# IR180-19_5GF.net
KiCad netlist of a schematic drawn in Altium Designer
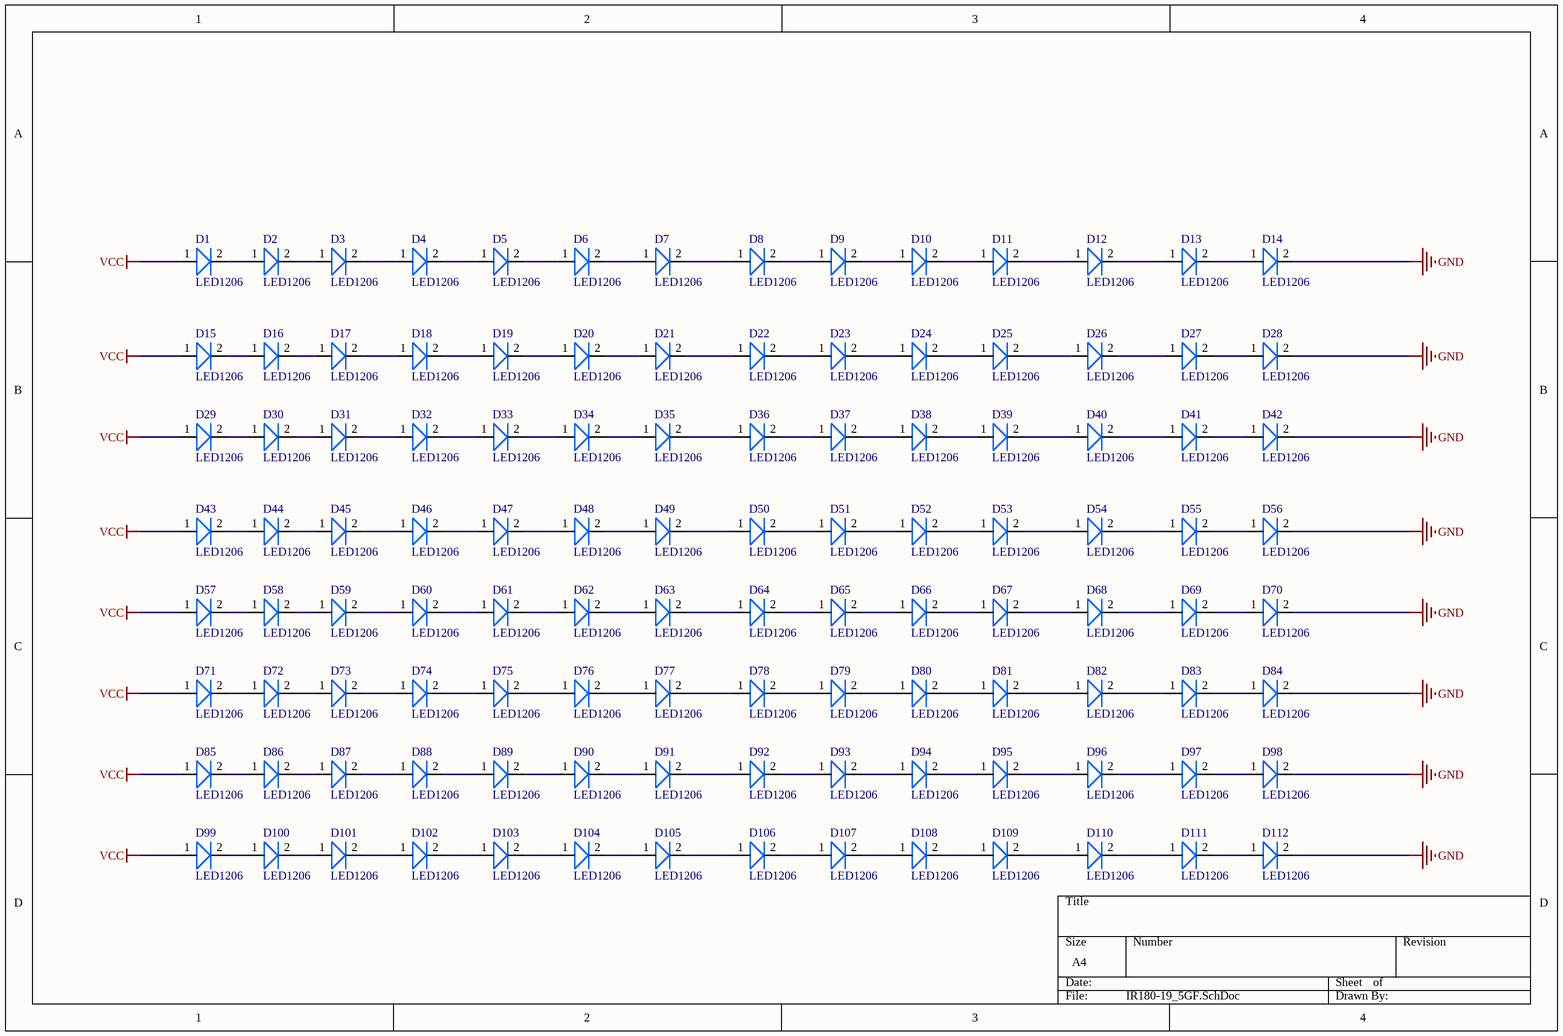
[diagram p0: IR180-19_5GF.SchDoc]

(export (version "E")
  (design (tool "Eeschema 10.0.6"))
  (components
    (comp (ref "D1")
      (value "LED1206")
      (footprint "myPCBLib:IRLED2835M")
      (libsource (lib "mySchLib") (part "LED1206"))
    )
    (comp (ref "D2")
      (value "LED1206")
      (footprint "myPCBLib:IRLED2835M")
      (libsource (lib "mySchLib") (part "LED1206"))
    )
    (comp (ref "D3")
      (value "LED1206")
      (footprint "myPCBLib:IRLED2835M")
      (libsource (lib "mySchLib") (part "LED1206"))
    )
    (comp (ref "D4")
      (value "LED1206")
      (footprint "myPCBLib:IRLED2835M")
      (libsource (lib "mySchLib") (part "LED1206"))
    )
    (comp (ref "D5")
      (value "LED1206")
      (footprint "myPCBLib:IRLED2835M")
      (libsource (lib "mySchLib") (part "LED1206"))
    )
    (comp (ref "D6")
      (value "LED1206")
      (footprint "myPCBLib:IRLED2835M")
      (libsource (lib "mySchLib") (part "LED1206"))
    )
    (comp (ref "D7")
      (value "LED1206")
      (footprint "myPCBLib:IRLED2835M")
      (libsource (lib "mySchLib") (part "LED1206"))
    )
    (comp (ref "D8")
      (value "LED1206")
      (footprint "myPCBLib:IRLED2835M")
      (libsource (lib "mySchLib") (part "LED1206"))
    )
    (comp (ref "D9")
      (value "LED1206")
      (footprint "myPCBLib:IRLED2835M")
      (libsource (lib "mySchLib") (part "LED1206"))
    )
    (comp (ref "D10")
      (value "LED1206")
      (footprint "myPCBLib:IRLED2835M")
      (libsource (lib "mySchLib") (part "LED1206"))
    )
    (comp (ref "D11")
      (value "LED1206")
      (footprint "myPCBLib:IRLED2835M")
      (libsource (lib "mySchLib") (part "LED1206"))
    )
    (comp (ref "D12")
      (value "LED1206")
      (footprint "myPCBLib:IRLED2835M")
      (libsource (lib "mySchLib") (part "LED1206"))
    )
    (comp (ref "D13")
      (value "LED1206")
      (footprint "myPCBLib:IRLED2835M")
      (libsource (lib "mySchLib") (part "LED1206"))
    )
    (comp (ref "D14")
      (value "LED1206")
      (footprint "myPCBLib:IRLED2835M")
      (libsource (lib "mySchLib") (part "LED1206"))
    )
    (comp (ref "D15")
      (value "LED1206")
      (footprint "myPCBLib:IRLED2835M")
      (libsource (lib "mySchLib") (part "LED1206"))
    )
    (comp (ref "D16")
      (value "LED1206")
      (footprint "myPCBLib:IRLED2835M")
      (libsource (lib "mySchLib") (part "LED1206"))
    )
    (comp (ref "D17")
      (value "LED1206")
      (footprint "myPCBLib:IRLED2835M")
      (libsource (lib "mySchLib") (part "LED1206"))
    )
    (comp (ref "D18")
      (value "LED1206")
      (footprint "myPCBLib:IRLED2835M")
      (libsource (lib "mySchLib") (part "LED1206"))
    )
    (comp (ref "D19")
      (value "LED1206")
      (footprint "myPCBLib:IRLED2835M")
      (libsource (lib "mySchLib") (part "LED1206"))
    )
    (comp (ref "D20")
      (value "LED1206")
      (footprint "myPCBLib:IRLED2835M")
      (libsource (lib "mySchLib") (part "LED1206"))
    )
    (comp (ref "D21")
      (value "LED1206")
      (footprint "myPCBLib:IRLED2835M")
      (libsource (lib "mySchLib") (part "LED1206"))
    )
    (comp (ref "D22")
      (value "LED1206")
      (footprint "myPCBLib:IRLED2835M")
      (libsource (lib "mySchLib") (part "LED1206"))
    )
    (comp (ref "D23")
      (value "LED1206")
      (footprint "myPCBLib:IRLED2835M")
      (libsource (lib "mySchLib") (part "LED1206"))
    )
    (comp (ref "D24")
      (value "LED1206")
      (footprint "myPCBLib:IRLED2835M")
      (libsource (lib "mySchLib") (part "LED1206"))
    )
    (comp (ref "D25")
      (value "LED1206")
      (footprint "myPCBLib:IRLED2835M")
      (libsource (lib "mySchLib") (part "LED1206"))
    )
    (comp (ref "D26")
      (value "LED1206")
      (footprint "myPCBLib:IRLED2835M")
      (libsource (lib "mySchLib") (part "LED1206"))
    )
    (comp (ref "D27")
      (value "LED1206")
      (footprint "myPCBLib:IRLED2835M")
      (libsource (lib "mySchLib") (part "LED1206"))
    )
    (comp (ref "D28")
      (value "LED1206")
      (footprint "myPCBLib:IRLED2835M")
      (libsource (lib "mySchLib") (part "LED1206"))
    )
    (comp (ref "D29")
      (value "LED1206")
      (footprint "myPCBLib:IRLED2835M")
      (libsource (lib "mySchLib") (part "LED1206"))
    )
    (comp (ref "D30")
      (value "LED1206")
      (footprint "myPCBLib:IRLED2835M")
      (libsource (lib "mySchLib") (part "LED1206"))
    )
    (comp (ref "D31")
      (value "LED1206")
      (footprint "myPCBLib:IRLED2835M")
      (libsource (lib "mySchLib") (part "LED1206"))
    )
    (comp (ref "D32")
      (value "LED1206")
      (footprint "myPCBLib:IRLED2835M")
      (libsource (lib "mySchLib") (part "LED1206"))
    )
    (comp (ref "D33")
      (value "LED1206")
      (footprint "myPCBLib:IRLED2835M")
      (libsource (lib "mySchLib") (part "LED1206"))
    )
    (comp (ref "D34")
      (value "LED1206")
      (footprint "myPCBLib:IRLED2835M")
      (libsource (lib "mySchLib") (part "LED1206"))
    )
    (comp (ref "D35")
      (value "LED1206")
      (footprint "myPCBLib:IRLED2835M")
      (libsource (lib "mySchLib") (part "LED1206"))
    )
    (comp (ref "D36")
      (value "LED1206")
      (footprint "myPCBLib:IRLED2835M")
      (libsource (lib "mySchLib") (part "LED1206"))
    )
    (comp (ref "D37")
      (value "LED1206")
      (footprint "myPCBLib:IRLED2835M")
      (libsource (lib "mySchLib") (part "LED1206"))
    )
    (comp (ref "D38")
      (value "LED1206")
      (footprint "myPCBLib:IRLED2835M")
      (libsource (lib "mySchLib") (part "LED1206"))
    )
    (comp (ref "D39")
      (value "LED1206")
      (footprint "myPCBLib:IRLED2835M")
      (libsource (lib "mySchLib") (part "LED1206"))
    )
    (comp (ref "D40")
      (value "LED1206")
      (footprint "myPCBLib:IRLED2835M")
      (libsource (lib "mySchLib") (part "LED1206"))
    )
    (comp (ref "D41")
      (value "LED1206")
      (footprint "myPCBLib:IRLED2835M")
      (libsource (lib "mySchLib") (part "LED1206"))
    )
    (comp (ref "D42")
      (value "LED1206")
      (footprint "myPCBLib:IRLED2835M")
      (libsource (lib "mySchLib") (part "LED1206"))
    )
    (comp (ref "D43")
      (value "LED1206")
      (footprint "myPCBLib:IRLED2835M")
      (libsource (lib "mySchLib") (part "LED1206"))
    )
    (comp (ref "D44")
      (value "LED1206")
      (footprint "myPCBLib:IRLED2835M")
      (libsource (lib "mySchLib") (part "LED1206"))
    )
    (comp (ref "D45")
      (value "LED1206")
      (footprint "myPCBLib:IRLED2835M")
      (libsource (lib "mySchLib") (part "LED1206"))
    )
    (comp (ref "D46")
      (value "LED1206")
      (footprint "myPCBLib:IRLED2835M")
      (libsource (lib "mySchLib") (part "LED1206"))
    )
    (comp (ref "D47")
      (value "LED1206")
      (footprint "myPCBLib:IRLED2835M")
      (libsource (lib "mySchLib") (part "LED1206"))
    )
    (comp (ref "D48")
      (value "LED1206")
      (footprint "myPCBLib:IRLED2835M")
      (libsource (lib "mySchLib") (part "LED1206"))
    )
    (comp (ref "D49")
      (value "LED1206")
      (footprint "myPCBLib:IRLED2835M")
      (libsource (lib "mySchLib") (part "LED1206"))
    )
    (comp (ref "D50")
      (value "LED1206")
      (footprint "myPCBLib:IRLED2835M")
      (libsource (lib "mySchLib") (part "LED1206"))
    )
    (comp (ref "D51")
      (value "LED1206")
      (footprint "myPCBLib:IRLED2835M")
      (libsource (lib "mySchLib") (part "LED1206"))
    )
    (comp (ref "D52")
      (value "LED1206")
      (footprint "myPCBLib:IRLED2835M")
      (libsource (lib "mySchLib") (part "LED1206"))
    )
    (comp (ref "D53")
      (value "LED1206")
      (footprint "myPCBLib:IRLED2835M")
      (libsource (lib "mySchLib") (part "LED1206"))
    )
    (comp (ref "D54")
      (value "LED1206")
      (footprint "myPCBLib:IRLED2835M")
      (libsource (lib "mySchLib") (part "LED1206"))
    )
    (comp (ref "D55")
      (value "LED1206")
      (footprint "myPCBLib:IRLED2835M")
      (libsource (lib "mySchLib") (part "LED1206"))
    )
    (comp (ref "D56")
      (value "LED1206")
      (footprint "myPCBLib:IRLED2835M")
      (libsource (lib "mySchLib") (part "LED1206"))
    )
    (comp (ref "D57")
      (value "LED1206")
      (footprint "myPCBLib:IRLED2835M")
      (libsource (lib "mySchLib") (part "LED1206"))
    )
    (comp (ref "D58")
      (value "LED1206")
      (footprint "myPCBLib:IRLED2835M")
      (libsource (lib "mySchLib") (part "LED1206"))
    )
    (comp (ref "D59")
      (value "LED1206")
      (footprint "myPCBLib:IRLED2835M")
      (libsource (lib "mySchLib") (part "LED1206"))
    )
    (comp (ref "D60")
      (value "LED1206")
      (footprint "myPCBLib:IRLED2835M")
      (libsource (lib "mySchLib") (part "LED1206"))
    )
    (comp (ref "D61")
      (value "LED1206")
      (footprint "myPCBLib:IRLED2835M")
      (libsource (lib "mySchLib") (part "LED1206"))
    )
    (comp (ref "D62")
      (value "LED1206")
      (footprint "myPCBLib:IRLED2835M")
      (libsource (lib "mySchLib") (part "LED1206"))
    )
    (comp (ref "D63")
      (value "LED1206")
      (footprint "myPCBLib:IRLED2835M")
      (libsource (lib "mySchLib") (part "LED1206"))
    )
    (comp (ref "D64")
      (value "LED1206")
      (footprint "myPCBLib:IRLED2835M")
      (libsource (lib "mySchLib") (part "LED1206"))
    )
    (comp (ref "D65")
      (value "LED1206")
      (footprint "myPCBLib:IRLED2835M")
      (libsource (lib "mySchLib") (part "LED1206"))
    )
    (comp (ref "D66")
      (value "LED1206")
      (footprint "myPCBLib:IRLED2835M")
      (libsource (lib "mySchLib") (part "LED1206"))
    )
    (comp (ref "D67")
      (value "LED1206")
      (footprint "myPCBLib:IRLED2835M")
      (libsource (lib "mySchLib") (part "LED1206"))
    )
    (comp (ref "D68")
      (value "LED1206")
      (footprint "myPCBLib:IRLED2835M")
      (libsource (lib "mySchLib") (part "LED1206"))
    )
    (comp (ref "D69")
      (value "LED1206")
      (footprint "myPCBLib:IRLED2835M")
      (libsource (lib "mySchLib") (part "LED1206"))
    )
    (comp (ref "D70")
      (value "LED1206")
      (footprint "myPCBLib:IRLED2835M")
      (libsource (lib "mySchLib") (part "LED1206"))
    )
    (comp (ref "D71")
      (value "LED1206")
      (footprint "myPCBLib:IRLED2835M")
      (libsource (lib "mySchLib") (part "LED1206"))
    )
    (comp (ref "D72")
      (value "LED1206")
      (footprint "myPCBLib:IRLED2835M")
      (libsource (lib "mySchLib") (part "LED1206"))
    )
    (comp (ref "D73")
      (value "LED1206")
      (footprint "myPCBLib:IRLED2835M")
      (libsource (lib "mySchLib") (part "LED1206"))
    )
    (comp (ref "D74")
      (value "LED1206")
      (footprint "myPCBLib:IRLED2835M")
      (libsource (lib "mySchLib") (part "LED1206"))
    )
    (comp (ref "D75")
      (value "LED1206")
      (footprint "myPCBLib:IRLED2835M")
      (libsource (lib "mySchLib") (part "LED1206"))
    )
    (comp (ref "D76")
      (value "LED1206")
      (footprint "myPCBLib:IRLED2835M")
      (libsource (lib "mySchLib") (part "LED1206"))
    )
    (comp (ref "D77")
      (value "LED1206")
      (footprint "myPCBLib:IRLED2835M")
      (libsource (lib "mySchLib") (part "LED1206"))
    )
    (comp (ref "D78")
      (value "LED1206")
      (footprint "myPCBLib:IRLED2835M")
      (libsource (lib "mySchLib") (part "LED1206"))
    )
    (comp (ref "D79")
      (value "LED1206")
      (footprint "myPCBLib:IRLED2835M")
      (libsource (lib "mySchLib") (part "LED1206"))
    )
    (comp (ref "D80")
      (value "LED1206")
      (footprint "myPCBLib:IRLED2835M")
      (libsource (lib "mySchLib") (part "LED1206"))
    )
    (comp (ref "D81")
      (value "LED1206")
      (footprint "myPCBLib:IRLED2835M")
      (libsource (lib "mySchLib") (part "LED1206"))
    )
    (comp (ref "D82")
      (value "LED1206")
      (footprint "myPCBLib:IRLED2835M")
      (libsource (lib "mySchLib") (part "LED1206"))
    )
    (comp (ref "D83")
      (value "LED1206")
      (footprint "myPCBLib:IRLED2835M")
      (libsource (lib "mySchLib") (part "LED1206"))
    )
    (comp (ref "D84")
      (value "LED1206")
      (footprint "myPCBLib:IRLED2835M")
      (libsource (lib "mySchLib") (part "LED1206"))
    )
    (comp (ref "D85")
      (value "LED1206")
      (footprint "myPCBLib:IRLED2835M")
      (libsource (lib "mySchLib") (part "LED1206"))
    )
    (comp (ref "D86")
      (value "LED1206")
      (footprint "myPCBLib:IRLED2835M")
      (libsource (lib "mySchLib") (part "LED1206"))
    )
    (comp (ref "D87")
      (value "LED1206")
      (footprint "myPCBLib:IRLED2835M")
      (libsource (lib "mySchLib") (part "LED1206"))
    )
    (comp (ref "D88")
      (value "LED1206")
      (footprint "myPCBLib:IRLED2835M")
      (libsource (lib "mySchLib") (part "LED1206"))
    )
    (comp (ref "D89")
      (value "LED1206")
      (footprint "myPCBLib:IRLED2835M")
      (libsource (lib "mySchLib") (part "LED1206"))
    )
    (comp (ref "D90")
      (value "LED1206")
      (footprint "myPCBLib:IRLED2835M")
      (libsource (lib "mySchLib") (part "LED1206"))
    )
    (comp (ref "D91")
      (value "LED1206")
      (footprint "myPCBLib:IRLED2835M")
      (libsource (lib "mySchLib") (part "LED1206"))
    )
    (comp (ref "D92")
      (value "LED1206")
      (footprint "myPCBLib:IRLED2835M")
      (libsource (lib "mySchLib") (part "LED1206"))
    )
    (comp (ref "D93")
      (value "LED1206")
      (footprint "myPCBLib:IRLED2835M")
      (libsource (lib "mySchLib") (part "LED1206"))
    )
    (comp (ref "D94")
      (value "LED1206")
      (footprint "myPCBLib:IRLED2835M")
      (libsource (lib "mySchLib") (part "LED1206"))
    )
    (comp (ref "D95")
      (value "LED1206")
      (footprint "myPCBLib:IRLED2835M")
      (libsource (lib "mySchLib") (part "LED1206"))
    )
    (comp (ref "D96")
      (value "LED1206")
      (footprint "myPCBLib:IRLED2835M")
      (libsource (lib "mySchLib") (part "LED1206"))
    )
    (comp (ref "D97")
      (value "LED1206")
      (footprint "myPCBLib:IRLED2835M")
      (libsource (lib "mySchLib") (part "LED1206"))
    )
    (comp (ref "D98")
      (value "LED1206")
      (footprint "myPCBLib:IRLED2835M")
      (libsource (lib "mySchLib") (part "LED1206"))
    )
    (comp (ref "D99")
      (value "LED1206")
      (footprint "myPCBLib:IRLED2835M")
      (libsource (lib "mySchLib") (part "LED1206"))
    )
    (comp (ref "D100")
      (value "LED1206")
      (footprint "myPCBLib:IRLED2835M")
      (libsource (lib "mySchLib") (part "LED1206"))
    )
    (comp (ref "D101")
      (value "LED1206")
      (footprint "myPCBLib:IRLED2835M")
      (libsource (lib "mySchLib") (part "LED1206"))
    )
    (comp (ref "D102")
      (value "LED1206")
      (footprint "myPCBLib:IRLED2835M")
      (libsource (lib "mySchLib") (part "LED1206"))
    )
    (comp (ref "D103")
      (value "LED1206")
      (footprint "myPCBLib:IRLED2835M")
      (libsource (lib "mySchLib") (part "LED1206"))
    )
    (comp (ref "D104")
      (value "LED1206")
      (footprint "myPCBLib:IRLED2835M")
      (libsource (lib "mySchLib") (part "LED1206"))
    )
    (comp (ref "D105")
      (value "LED1206")
      (footprint "myPCBLib:IRLED2835M")
      (libsource (lib "mySchLib") (part "LED1206"))
    )
    (comp (ref "D106")
      (value "LED1206")
      (footprint "myPCBLib:IRLED2835M")
      (libsource (lib "mySchLib") (part "LED1206"))
    )
    (comp (ref "D107")
      (value "LED1206")
      (footprint "myPCBLib:IRLED2835M")
      (libsource (lib "mySchLib") (part "LED1206"))
    )
    (comp (ref "D108")
      (value "LED1206")
      (footprint "myPCBLib:IRLED2835M")
      (libsource (lib "mySchLib") (part "LED1206"))
    )
    (comp (ref "D109")
      (value "LED1206")
      (footprint "myPCBLib:IRLED2835M")
      (libsource (lib "mySchLib") (part "LED1206"))
    )
    (comp (ref "D110")
      (value "LED1206")
      (footprint "myPCBLib:IRLED2835M")
      (libsource (lib "mySchLib") (part "LED1206"))
    )
    (comp (ref "D111")
      (value "LED1206")
      (footprint "myPCBLib:IRLED2835M")
      (libsource (lib "mySchLib") (part "LED1206"))
    )
    (comp (ref "D112")
      (value "LED1206")
      (footprint "myPCBLib:IRLED2835M")
      (libsource (lib "mySchLib") (part "LED1206"))
    )
  )
  (nets
    (net (code "1") (name "GND") (class "Default")
      (node (ref "D112") (pin "2") (pinfunction "-_2") (pintype "open_collector"))
      (node (ref "D14") (pin "2") (pinfunction "-_2") (pintype "open_collector"))
      (node (ref "D28") (pin "2") (pinfunction "-_2") (pintype "open_collector"))
      (node (ref "D42") (pin "2") (pinfunction "-_2") (pintype "open_collector"))
      (node (ref "D56") (pin "2") (pinfunction "-_2") (pintype "open_collector"))
      (node (ref "D70") (pin "2") (pinfunction "-_2") (pintype "open_collector"))
      (node (ref "D84") (pin "2") (pinfunction "-_2") (pintype "open_collector"))
      (node (ref "D98") (pin "2") (pinfunction "-_2") (pintype "open_collector"))
    )
    (net (code "2") (name "Net-(D1--)") (class "Default")
      (node (ref "D1") (pin "2") (pinfunction "-_2") (pintype "open_collector"))
      (node (ref "D2") (pin "1") (pinfunction "+_1") (pintype "passive"))
    )
    (net (code "3") (name "Net-(D2--)") (class "Default")
      (node (ref "D2") (pin "2") (pinfunction "-_2") (pintype "open_collector"))
      (node (ref "D3") (pin "1") (pinfunction "+_1") (pintype "passive"))
    )
    (net (code "4") (name "Net-(D3--)") (class "Default")
      (node (ref "D3") (pin "2") (pinfunction "-_2") (pintype "open_collector"))
      (node (ref "D4") (pin "1") (pinfunction "+_1") (pintype "passive"))
    )
    (net (code "5") (name "Net-(D4--)") (class "Default")
      (node (ref "D4") (pin "2") (pinfunction "-_2") (pintype "open_collector"))
      (node (ref "D5") (pin "1") (pinfunction "+_1") (pintype "passive"))
    )
    (net (code "6") (name "Net-(D5--)") (class "Default")
      (node (ref "D5") (pin "2") (pinfunction "-_2") (pintype "open_collector"))
      (node (ref "D6") (pin "1") (pinfunction "+_1") (pintype "passive"))
    )
    (net (code "7") (name "Net-(D6--)") (class "Default")
      (node (ref "D6") (pin "2") (pinfunction "-_2") (pintype "open_collector"))
      (node (ref "D7") (pin "1") (pinfunction "+_1") (pintype "passive"))
    )
    (net (code "8") (name "Net-(D7--)") (class "Default")
      (node (ref "D7") (pin "2") (pinfunction "-_2") (pintype "open_collector"))
      (node (ref "D8") (pin "1") (pinfunction "+_1") (pintype "passive"))
    )
    (net (code "9") (name "Net-(D8--)") (class "Default")
      (node (ref "D8") (pin "2") (pinfunction "-_2") (pintype "open_collector"))
      (node (ref "D9") (pin "1") (pinfunction "+_1") (pintype "passive"))
    )
    (net (code "10") (name "Net-(D10-+)") (class "Default")
      (node (ref "D10") (pin "1") (pinfunction "+_1") (pintype "passive"))
      (node (ref "D9") (pin "2") (pinfunction "-_2") (pintype "open_collector"))
    )
    (net (code "11") (name "Net-(D10--)") (class "Default")
      (node (ref "D10") (pin "2") (pinfunction "-_2") (pintype "open_collector"))
      (node (ref "D11") (pin "1") (pinfunction "+_1") (pintype "passive"))
    )
    (net (code "12") (name "Net-(D11--)") (class "Default")
      (node (ref "D11") (pin "2") (pinfunction "-_2") (pintype "open_collector"))
      (node (ref "D12") (pin "1") (pinfunction "+_1") (pintype "passive"))
    )
    (net (code "13") (name "Net-(D12--)") (class "Default")
      (node (ref "D12") (pin "2") (pinfunction "-_2") (pintype "open_collector"))
      (node (ref "D13") (pin "1") (pinfunction "+_1") (pintype "passive"))
    )
    (net (code "14") (name "Net-(D13--)") (class "Default")
      (node (ref "D13") (pin "2") (pinfunction "-_2") (pintype "open_collector"))
      (node (ref "D14") (pin "1") (pinfunction "+_1") (pintype "passive"))
    )
    (net (code "15") (name "Net-(D15--)") (class "Default")
      (node (ref "D15") (pin "2") (pinfunction "-_2") (pintype "open_collector"))
      (node (ref "D16") (pin "1") (pinfunction "+_1") (pintype "passive"))
    )
    (net (code "16") (name "Net-(D16--)") (class "Default")
      (node (ref "D16") (pin "2") (pinfunction "-_2") (pintype "open_collector"))
      (node (ref "D17") (pin "1") (pinfunction "+_1") (pintype "passive"))
    )
    (net (code "17") (name "Net-(D17--)") (class "Default")
      (node (ref "D17") (pin "2") (pinfunction "-_2") (pintype "open_collector"))
      (node (ref "D18") (pin "1") (pinfunction "+_1") (pintype "passive"))
    )
    (net (code "18") (name "Net-(D18--)") (class "Default")
      (node (ref "D18") (pin "2") (pinfunction "-_2") (pintype "open_collector"))
      (node (ref "D19") (pin "1") (pinfunction "+_1") (pintype "passive"))
    )
    (net (code "19") (name "Net-(D19--)") (class "Default")
      (node (ref "D19") (pin "2") (pinfunction "-_2") (pintype "open_collector"))
      (node (ref "D20") (pin "1") (pinfunction "+_1") (pintype "passive"))
    )
    (net (code "20") (name "Net-(D20--)") (class "Default")
      (node (ref "D20") (pin "2") (pinfunction "-_2") (pintype "open_collector"))
      (node (ref "D21") (pin "1") (pinfunction "+_1") (pintype "passive"))
    )
    (net (code "21") (name "Net-(D21--)") (class "Default")
      (node (ref "D21") (pin "2") (pinfunction "-_2") (pintype "open_collector"))
      (node (ref "D22") (pin "1") (pinfunction "+_1") (pintype "passive"))
    )
    (net (code "22") (name "Net-(D22--)") (class "Default")
      (node (ref "D22") (pin "2") (pinfunction "-_2") (pintype "open_collector"))
      (node (ref "D23") (pin "1") (pinfunction "+_1") (pintype "passive"))
    )
    (net (code "23") (name "Net-(D23--)") (class "Default")
      (node (ref "D23") (pin "2") (pinfunction "-_2") (pintype "open_collector"))
      (node (ref "D24") (pin "1") (pinfunction "+_1") (pintype "passive"))
    )
    (net (code "24") (name "Net-(D24--)") (class "Default")
      (node (ref "D24") (pin "2") (pinfunction "-_2") (pintype "open_collector"))
      (node (ref "D25") (pin "1") (pinfunction "+_1") (pintype "passive"))
    )
    (net (code "25") (name "Net-(D25--)") (class "Default")
      (node (ref "D25") (pin "2") (pinfunction "-_2") (pintype "open_collector"))
      (node (ref "D26") (pin "1") (pinfunction "+_1") (pintype "passive"))
    )
    (net (code "26") (name "Net-(D26--)") (class "Default")
      (node (ref "D26") (pin "2") (pinfunction "-_2") (pintype "open_collector"))
      (node (ref "D27") (pin "1") (pinfunction "+_1") (pintype "passive"))
    )
    (net (code "27") (name "Net-(D27--)") (class "Default")
      (node (ref "D27") (pin "2") (pinfunction "-_2") (pintype "open_collector"))
      (node (ref "D28") (pin "1") (pinfunction "+_1") (pintype "passive"))
    )
    (net (code "28") (name "Net-(D29--)") (class "Default")
      (node (ref "D29") (pin "2") (pinfunction "-_2") (pintype "open_collector"))
      (node (ref "D30") (pin "1") (pinfunction "+_1") (pintype "passive"))
    )
    (net (code "29") (name "Net-(D30--)") (class "Default")
      (node (ref "D30") (pin "2") (pinfunction "-_2") (pintype "open_collector"))
      (node (ref "D31") (pin "1") (pinfunction "+_1") (pintype "passive"))
    )
    (net (code "30") (name "Net-(D31--)") (class "Default")
      (node (ref "D31") (pin "2") (pinfunction "-_2") (pintype "open_collector"))
      (node (ref "D32") (pin "1") (pinfunction "+_1") (pintype "passive"))
    )
    (net (code "31") (name "Net-(D32--)") (class "Default")
      (node (ref "D32") (pin "2") (pinfunction "-_2") (pintype "open_collector"))
      (node (ref "D33") (pin "1") (pinfunction "+_1") (pintype "passive"))
    )
    (net (code "32") (name "Net-(D33--)") (class "Default")
      (node (ref "D33") (pin "2") (pinfunction "-_2") (pintype "open_collector"))
      (node (ref "D34") (pin "1") (pinfunction "+_1") (pintype "passive"))
    )
    (net (code "33") (name "Net-(D34--)") (class "Default")
      (node (ref "D34") (pin "2") (pinfunction "-_2") (pintype "open_collector"))
      (node (ref "D35") (pin "1") (pinfunction "+_1") (pintype "passive"))
    )
    (net (code "34") (name "Net-(D35--)") (class "Default")
      (node (ref "D35") (pin "2") (pinfunction "-_2") (pintype "open_collector"))
      (node (ref "D36") (pin "1") (pinfunction "+_1") (pintype "passive"))
    )
    (net (code "35") (name "Net-(D36--)") (class "Default")
      (node (ref "D36") (pin "2") (pinfunction "-_2") (pintype "open_collector"))
      (node (ref "D37") (pin "1") (pinfunction "+_1") (pintype "passive"))
    )
    (net (code "36") (name "Net-(D37--)") (class "Default")
      (node (ref "D37") (pin "2") (pinfunction "-_2") (pintype "open_collector"))
      (node (ref "D38") (pin "1") (pinfunction "+_1") (pintype "passive"))
    )
    (net (code "37") (name "Net-(D38--)") (class "Default")
      (node (ref "D38") (pin "2") (pinfunction "-_2") (pintype "open_collector"))
      (node (ref "D39") (pin "1") (pinfunction "+_1") (pintype "passive"))
    )
    (net (code "38") (name "Net-(D39--)") (class "Default")
      (node (ref "D39") (pin "2") (pinfunction "-_2") (pintype "open_collector"))
      (node (ref "D40") (pin "1") (pinfunction "+_1") (pintype "passive"))
    )
    (net (code "39") (name "Net-(D40--)") (class "Default")
      (node (ref "D40") (pin "2") (pinfunction "-_2") (pintype "open_collector"))
      (node (ref "D41") (pin "1") (pinfunction "+_1") (pintype "passive"))
    )
    (net (code "40") (name "Net-(D41--)") (class "Default")
      (node (ref "D41") (pin "2") (pinfunction "-_2") (pintype "open_collector"))
      (node (ref "D42") (pin "1") (pinfunction "+_1") (pintype "passive"))
    )
    (net (code "41") (name "Net-(D43--)") (class "Default")
      (node (ref "D43") (pin "2") (pinfunction "-_2") (pintype "open_collector"))
      (node (ref "D44") (pin "1") (pinfunction "+_1") (pintype "passive"))
    )
    (net (code "42") (name "Net-(D44--)") (class "Default")
      (node (ref "D44") (pin "2") (pinfunction "-_2") (pintype "open_collector"))
      (node (ref "D45") (pin "1") (pinfunction "+_1") (pintype "passive"))
    )
    (net (code "43") (name "Net-(D45--)") (class "Default")
      (node (ref "D45") (pin "2") (pinfunction "-_2") (pintype "open_collector"))
      (node (ref "D46") (pin "1") (pinfunction "+_1") (pintype "passive"))
    )
    (net (code "44") (name "Net-(D46--)") (class "Default")
      (node (ref "D46") (pin "2") (pinfunction "-_2") (pintype "open_collector"))
      (node (ref "D47") (pin "1") (pinfunction "+_1") (pintype "passive"))
    )
    (net (code "45") (name "Net-(D47--)") (class "Default")
      (node (ref "D47") (pin "2") (pinfunction "-_2") (pintype "open_collector"))
      (node (ref "D48") (pin "1") (pinfunction "+_1") (pintype "passive"))
    )
    (net (code "46") (name "Net-(D48--)") (class "Default")
      (node (ref "D48") (pin "2") (pinfunction "-_2") (pintype "open_collector"))
      (node (ref "D49") (pin "1") (pinfunction "+_1") (pintype "passive"))
    )
    (net (code "47") (name "Net-(D49--)") (class "Default")
      (node (ref "D49") (pin "2") (pinfunction "-_2") (pintype "open_collector"))
      (node (ref "D50") (pin "1") (pinfunction "+_1") (pintype "passive"))
    )
    (net (code "48") (name "Net-(D50--)") (class "Default")
      (node (ref "D50") (pin "2") (pinfunction "-_2") (pintype "open_collector"))
      (node (ref "D51") (pin "1") (pinfunction "+_1") (pintype "passive"))
    )
    (net (code "49") (name "Net-(D51--)") (class "Default")
      (node (ref "D51") (pin "2") (pinfunction "-_2") (pintype "open_collector"))
      (node (ref "D52") (pin "1") (pinfunction "+_1") (pintype "passive"))
    )
    (net (code "50") (name "Net-(D52--)") (class "Default")
      (node (ref "D52") (pin "2") (pinfunction "-_2") (pintype "open_collector"))
      (node (ref "D53") (pin "1") (pinfunction "+_1") (pintype "passive"))
    )
    (net (code "51") (name "Net-(D53--)") (class "Default")
      (node (ref "D53") (pin "2") (pinfunction "-_2") (pintype "open_collector"))
      (node (ref "D54") (pin "1") (pinfunction "+_1") (pintype "passive"))
    )
    (net (code "52") (name "Net-(D54--)") (class "Default")
      (node (ref "D54") (pin "2") (pinfunction "-_2") (pintype "open_collector"))
      (node (ref "D55") (pin "1") (pinfunction "+_1") (pintype "passive"))
    )
    (net (code "53") (name "Net-(D55--)") (class "Default")
      (node (ref "D55") (pin "2") (pinfunction "-_2") (pintype "open_collector"))
      (node (ref "D56") (pin "1") (pinfunction "+_1") (pintype "passive"))
    )
    (net (code "54") (name "Net-(D57--)") (class "Default")
      (node (ref "D57") (pin "2") (pinfunction "-_2") (pintype "open_collector"))
      (node (ref "D58") (pin "1") (pinfunction "+_1") (pintype "passive"))
    )
    (net (code "55") (name "Net-(D58--)") (class "Default")
      (node (ref "D58") (pin "2") (pinfunction "-_2") (pintype "open_collector"))
      (node (ref "D59") (pin "1") (pinfunction "+_1") (pintype "passive"))
    )
    (net (code "56") (name "Net-(D59--)") (class "Default")
      (node (ref "D59") (pin "2") (pinfunction "-_2") (pintype "open_collector"))
      (node (ref "D60") (pin "1") (pinfunction "+_1") (pintype "passive"))
    )
    (net (code "57") (name "Net-(D60--)") (class "Default")
      (node (ref "D60") (pin "2") (pinfunction "-_2") (pintype "open_collector"))
      (node (ref "D61") (pin "1") (pinfunction "+_1") (pintype "passive"))
    )
    (net (code "58") (name "Net-(D61--)") (class "Default")
      (node (ref "D61") (pin "2") (pinfunction "-_2") (pintype "open_collector"))
      (node (ref "D62") (pin "1") (pinfunction "+_1") (pintype "passive"))
    )
    (net (code "59") (name "Net-(D62--)") (class "Default")
      (node (ref "D62") (pin "2") (pinfunction "-_2") (pintype "open_collector"))
      (node (ref "D63") (pin "1") (pinfunction "+_1") (pintype "passive"))
    )
    (net (code "60") (name "Net-(D63--)") (class "Default")
      (node (ref "D63") (pin "2") (pinfunction "-_2") (pintype "open_collector"))
      (node (ref "D64") (pin "1") (pinfunction "+_1") (pintype "passive"))
    )
    (net (code "61") (name "Net-(D64--)") (class "Default")
      (node (ref "D64") (pin "2") (pinfunction "-_2") (pintype "open_collector"))
      (node (ref "D65") (pin "1") (pinfunction "+_1") (pintype "passive"))
    )
    (net (code "62") (name "Net-(D65--)") (class "Default")
      (node (ref "D65") (pin "2") (pinfunction "-_2") (pintype "open_collector"))
      (node (ref "D66") (pin "1") (pinfunction "+_1") (pintype "passive"))
    )
    (net (code "63") (name "Net-(D66--)") (class "Default")
      (node (ref "D66") (pin "2") (pinfunction "-_2") (pintype "open_collector"))
      (node (ref "D67") (pin "1") (pinfunction "+_1") (pintype "passive"))
    )
    (net (code "64") (name "Net-(D67--)") (class "Default")
      (node (ref "D67") (pin "2") (pinfunction "-_2") (pintype "open_collector"))
      (node (ref "D68") (pin "1") (pinfunction "+_1") (pintype "passive"))
    )
    (net (code "65") (name "Net-(D68--)") (class "Default")
      (node (ref "D68") (pin "2") (pinfunction "-_2") (pintype "open_collector"))
      (node (ref "D69") (pin "1") (pinfunction "+_1") (pintype "passive"))
    )
    (net (code "66") (name "Net-(D69--)") (class "Default")
      (node (ref "D69") (pin "2") (pinfunction "-_2") (pintype "open_collector"))
      (node (ref "D70") (pin "1") (pinfunction "+_1") (pintype "passive"))
    )
    (net (code "67") (name "Net-(D71--)") (class "Default")
      (node (ref "D71") (pin "2") (pinfunction "-_2") (pintype "open_collector"))
      (node (ref "D72") (pin "1") (pinfunction "+_1") (pintype "passive"))
    )
    (net (code "68") (name "Net-(D72--)") (class "Default")
      (node (ref "D72") (pin "2") (pinfunction "-_2") (pintype "open_collector"))
      (node (ref "D73") (pin "1") (pinfunction "+_1") (pintype "passive"))
    )
    (net (code "69") (name "Net-(D73--)") (class "Default")
      (node (ref "D73") (pin "2") (pinfunction "-_2") (pintype "open_collector"))
      (node (ref "D74") (pin "1") (pinfunction "+_1") (pintype "passive"))
    )
    (net (code "70") (name "Net-(D74--)") (class "Default")
      (node (ref "D74") (pin "2") (pinfunction "-_2") (pintype "open_collector"))
      (node (ref "D75") (pin "1") (pinfunction "+_1") (pintype "passive"))
    )
    (net (code "71") (name "Net-(D75--)") (class "Default")
      (node (ref "D75") (pin "2") (pinfunction "-_2") (pintype "open_collector"))
      (node (ref "D76") (pin "1") (pinfunction "+_1") (pintype "passive"))
    )
    (net (code "72") (name "Net-(D76--)") (class "Default")
      (node (ref "D76") (pin "2") (pinfunction "-_2") (pintype "open_collector"))
      (node (ref "D77") (pin "1") (pinfunction "+_1") (pintype "passive"))
    )
    (net (code "73") (name "Net-(D77--)") (class "Default")
      (node (ref "D77") (pin "2") (pinfunction "-_2") (pintype "open_collector"))
      (node (ref "D78") (pin "1") (pinfunction "+_1") (pintype "passive"))
    )
    (net (code "74") (name "Net-(D78--)") (class "Default")
      (node (ref "D78") (pin "2") (pinfunction "-_2") (pintype "open_collector"))
      (node (ref "D79") (pin "1") (pinfunction "+_1") (pintype "passive"))
    )
    (net (code "75") (name "Net-(D79--)") (class "Default")
      (node (ref "D79") (pin "2") (pinfunction "-_2") (pintype "open_collector"))
      (node (ref "D80") (pin "1") (pinfunction "+_1") (pintype "passive"))
    )
    (net (code "76") (name "Net-(D80--)") (class "Default")
      (node (ref "D80") (pin "2") (pinfunction "-_2") (pintype "open_collector"))
      (node (ref "D81") (pin "1") (pinfunction "+_1") (pintype "passive"))
    )
    (net (code "77") (name "Net-(D81--)") (class "Default")
      (node (ref "D81") (pin "2") (pinfunction "-_2") (pintype "open_collector"))
      (node (ref "D82") (pin "1") (pinfunction "+_1") (pintype "passive"))
    )
    (net (code "78") (name "Net-(D82--)") (class "Default")
      (node (ref "D82") (pin "2") (pinfunction "-_2") (pintype "open_collector"))
      (node (ref "D83") (pin "1") (pinfunction "+_1") (pintype "passive"))
    )
    (net (code "79") (name "Net-(D83--)") (class "Default")
      (node (ref "D83") (pin "2") (pinfunction "-_2") (pintype "open_collector"))
      (node (ref "D84") (pin "1") (pinfunction "+_1") (pintype "passive"))
    )
    (net (code "80") (name "Net-(D85--)") (class "Default")
      (node (ref "D85") (pin "2") (pinfunction "-_2") (pintype "open_collector"))
      (node (ref "D86") (pin "1") (pinfunction "+_1") (pintype "passive"))
    )
    (net (code "81") (name "Net-(D86--)") (class "Default")
      (node (ref "D86") (pin "2") (pinfunction "-_2") (pintype "open_collector"))
      (node (ref "D87") (pin "1") (pinfunction "+_1") (pintype "passive"))
    )
    (net (code "82") (name "Net-(D87--)") (class "Default")
      (node (ref "D87") (pin "2") (pinfunction "-_2") (pintype "open_collector"))
      (node (ref "D88") (pin "1") (pinfunction "+_1") (pintype "passive"))
    )
    (net (code "83") (name "Net-(D88--)") (class "Default")
      (node (ref "D88") (pin "2") (pinfunction "-_2") (pintype "open_collector"))
      (node (ref "D89") (pin "1") (pinfunction "+_1") (pintype "passive"))
    )
    (net (code "84") (name "Net-(D89--)") (class "Default")
      (node (ref "D89") (pin "2") (pinfunction "-_2") (pintype "open_collector"))
      (node (ref "D90") (pin "1") (pinfunction "+_1") (pintype "passive"))
    )
    (net (code "85") (name "Net-(D90--)") (class "Default")
      (node (ref "D90") (pin "2") (pinfunction "-_2") (pintype "open_collector"))
      (node (ref "D91") (pin "1") (pinfunction "+_1") (pintype "passive"))
    )
    (net (code "86") (name "Net-(D91--)") (class "Default")
      (node (ref "D91") (pin "2") (pinfunction "-_2") (pintype "open_collector"))
      (node (ref "D92") (pin "1") (pinfunction "+_1") (pintype "passive"))
    )
    (net (code "87") (name "Net-(D92--)") (class "Default")
      (node (ref "D92") (pin "2") (pinfunction "-_2") (pintype "open_collector"))
      (node (ref "D93") (pin "1") (pinfunction "+_1") (pintype "passive"))
    )
    (net (code "88") (name "Net-(D93--)") (class "Default")
      (node (ref "D93") (pin "2") (pinfunction "-_2") (pintype "open_collector"))
      (node (ref "D94") (pin "1") (pinfunction "+_1") (pintype "passive"))
    )
    (net (code "89") (name "Net-(D94--)") (class "Default")
      (node (ref "D94") (pin "2") (pinfunction "-_2") (pintype "open_collector"))
      (node (ref "D95") (pin "1") (pinfunction "+_1") (pintype "passive"))
    )
    (net (code "90") (name "Net-(D95--)") (class "Default")
      (node (ref "D95") (pin "2") (pinfunction "-_2") (pintype "open_collector"))
      (node (ref "D96") (pin "1") (pinfunction "+_1") (pintype "passive"))
    )
    (net (code "91") (name "Net-(D96--)") (class "Default")
      (node (ref "D96") (pin "2") (pinfunction "-_2") (pintype "open_collector"))
      (node (ref "D97") (pin "1") (pinfunction "+_1") (pintype "passive"))
    )
    (net (code "92") (name "Net-(D97--)") (class "Default")
      (node (ref "D97") (pin "2") (pinfunction "-_2") (pintype "open_collector"))
      (node (ref "D98") (pin "1") (pinfunction "+_1") (pintype "passive"))
    )
    (net (code "93") (name "Net-(D100-+)") (class "Default")
      (node (ref "D100") (pin "1") (pinfunction "+_1") (pintype "passive"))
      (node (ref "D99") (pin "2") (pinfunction "-_2") (pintype "open_collector"))
    )
    (net (code "94") (name "Net-(D100--)") (class "Default")
      (node (ref "D100") (pin "2") (pinfunction "-_2") (pintype "open_collector"))
      (node (ref "D101") (pin "1") (pinfunction "+_1") (pintype "passive"))
    )
    (net (code "95") (name "Net-(D101--)") (class "Default")
      (node (ref "D101") (pin "2") (pinfunction "-_2") (pintype "open_collector"))
      (node (ref "D102") (pin "1") (pinfunction "+_1") (pintype "passive"))
    )
    (net (code "96") (name "Net-(D102--)") (class "Default")
      (node (ref "D102") (pin "2") (pinfunction "-_2") (pintype "open_collector"))
      (node (ref "D103") (pin "1") (pinfunction "+_1") (pintype "passive"))
    )
    (net (code "97") (name "Net-(D103--)") (class "Default")
      (node (ref "D103") (pin "2") (pinfunction "-_2") (pintype "open_collector"))
      (node (ref "D104") (pin "1") (pinfunction "+_1") (pintype "passive"))
    )
    (net (code "98") (name "Net-(D104--)") (class "Default")
      (node (ref "D104") (pin "2") (pinfunction "-_2") (pintype "open_collector"))
      (node (ref "D105") (pin "1") (pinfunction "+_1") (pintype "passive"))
    )
    (net (code "99") (name "Net-(D105--)") (class "Default")
      (node (ref "D105") (pin "2") (pinfunction "-_2") (pintype "open_collector"))
      (node (ref "D106") (pin "1") (pinfunction "+_1") (pintype "passive"))
    )
    (net (code "100") (name "Net-(D106--)") (class "Default")
      (node (ref "D106") (pin "2") (pinfunction "-_2") (pintype "open_collector"))
      (node (ref "D107") (pin "1") (pinfunction "+_1") (pintype "passive"))
    )
    (net (code "101") (name "Net-(D107--)") (class "Default")
      (node (ref "D107") (pin "2") (pinfunction "-_2") (pintype "open_collector"))
      (node (ref "D108") (pin "1") (pinfunction "+_1") (pintype "passive"))
    )
    (net (code "102") (name "Net-(D108--)") (class "Default")
      (node (ref "D108") (pin "2") (pinfunction "-_2") (pintype "open_collector"))
      (node (ref "D109") (pin "1") (pinfunction "+_1") (pintype "passive"))
    )
    (net (code "103") (name "Net-(D109--)") (class "Default")
      (node (ref "D109") (pin "2") (pinfunction "-_2") (pintype "open_collector"))
      (node (ref "D110") (pin "1") (pinfunction "+_1") (pintype "passive"))
    )
    (net (code "104") (name "Net-(D110--)") (class "Default")
      (node (ref "D110") (pin "2") (pinfunction "-_2") (pintype "open_collector"))
      (node (ref "D111") (pin "1") (pinfunction "+_1") (pintype "passive"))
    )
    (net (code "105") (name "Net-(D111--)") (class "Default")
      (node (ref "D111") (pin "2") (pinfunction "-_2") (pintype "open_collector"))
      (node (ref "D112") (pin "1") (pinfunction "+_1") (pintype "passive"))
    )
    (net (code "106") (name "VCC") (class "Default")
      (node (ref "D1") (pin "1") (pinfunction "+_1") (pintype "passive"))
      (node (ref "D15") (pin "1") (pinfunction "+_1") (pintype "passive"))
      (node (ref "D29") (pin "1") (pinfunction "+_1") (pintype "passive"))
      (node (ref "D43") (pin "1") (pinfunction "+_1") (pintype "passive"))
      (node (ref "D57") (pin "1") (pinfunction "+_1") (pintype "passive"))
      (node (ref "D71") (pin "1") (pinfunction "+_1") (pintype "passive"))
      (node (ref "D85") (pin "1") (pinfunction "+_1") (pintype "passive"))
      (node (ref "D99") (pin "1") (pinfunction "+_1") (pintype "passive"))
    )
  )
)
